# Cpcis_connectors_P1_P2_P3.net
KiCad netlist of a schematic drawn in Altium Designer
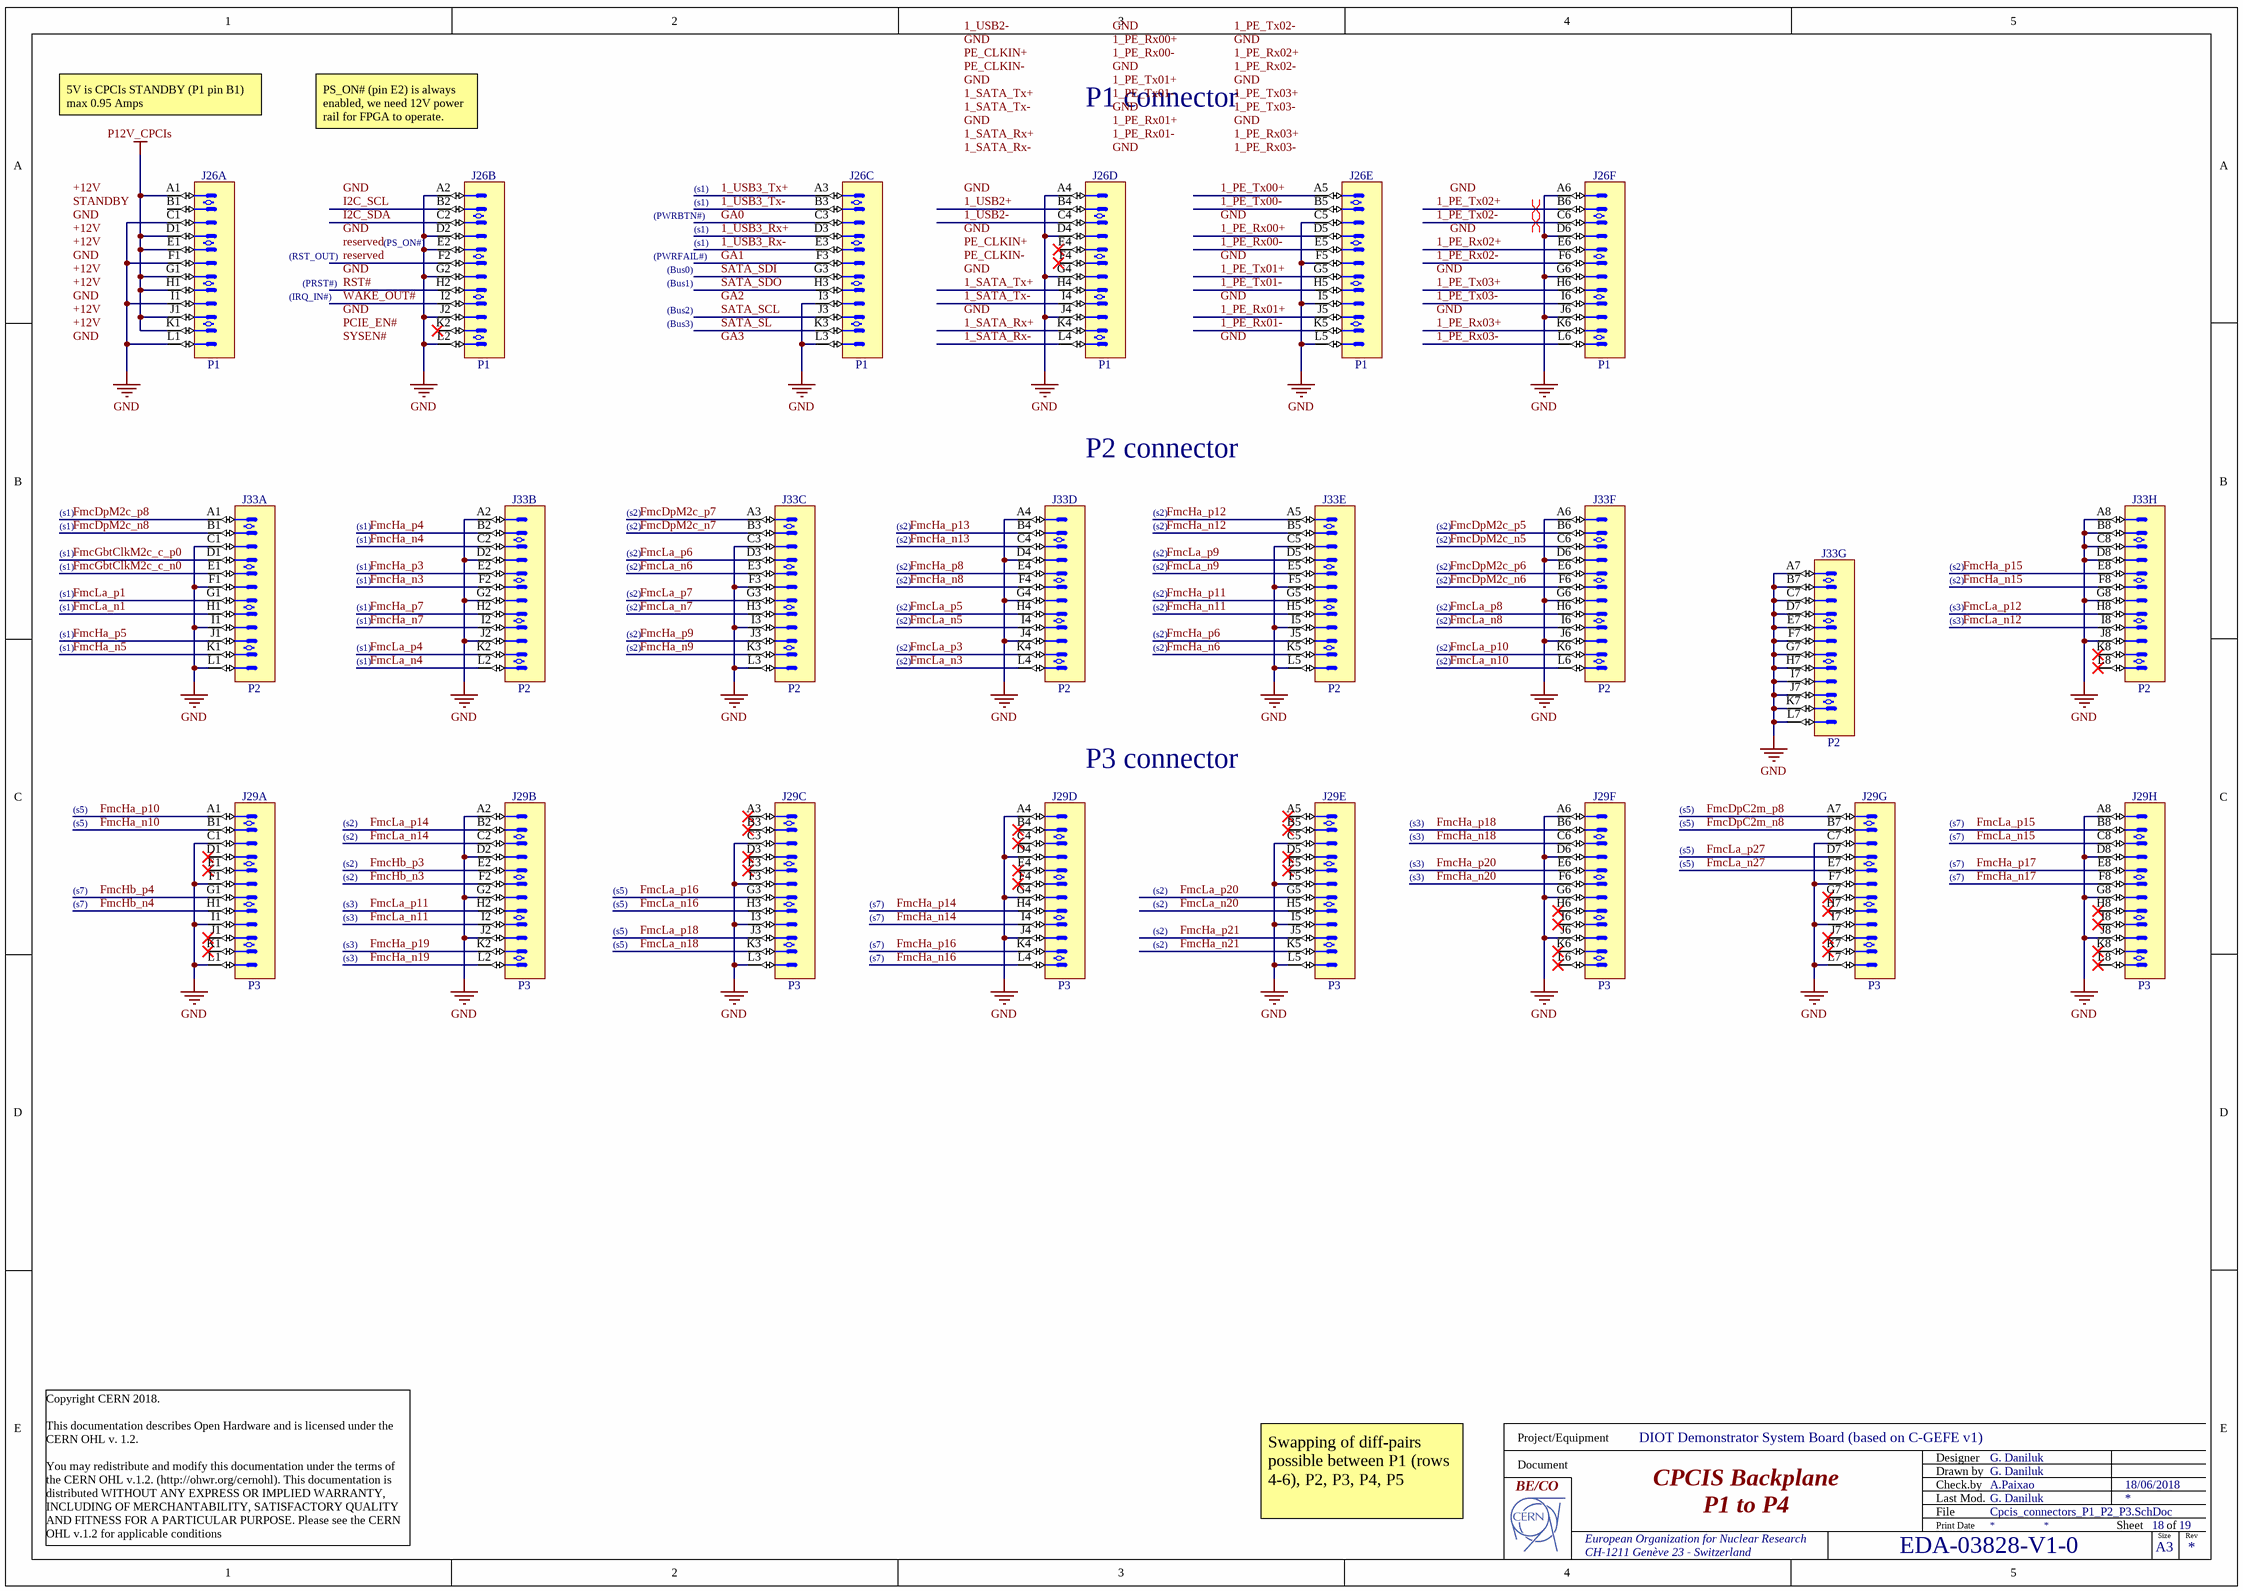
[diagram p0: Cpcis_connectors_P1_P2_P3.SchDoc]

(export (version "E")
  (design (tool "Eeschema 10.0.6"))
  (components
    (comp (ref "J26")
      (value "P1")
      (footprint "AMPHENOL_10052825-101LF")
      (description "72 Contacts Header, 6 Columns, 4 Pairs per Column")
      (fields
        (field (name "PART NUMBER") "AMPHENOL_10052825-101LF")
        (field (name "MANUFACTURER") "AMPHENOL")
        (field (name "AUTHOR") "CERN DEM MR")
      )
      (libsource (lib "Connectors") (part "AMPHENOL_10052825-101LF"))
    )
    (comp (ref "J29")
      (value "P3")
      (footprint "AMPHENOL_10052837-101LF")
      (description "96 Contacts Header, 8 Columns, 4 Pairs per Column")
      (fields
        (field (name "PART NUMBER") "AMPHENOL_10052837-101LF")
        (field (name "MANUFACTURER") "AMPHENOL")
        (field (name "AUTHOR") "CERN DEM MR")
      )
      (libsource (lib "Connectors") (part "AMPHENOL_10052837-101LF"))
    )
    (comp (ref "J33")
      (value "P2")
      (footprint "AMPHENOL_10052837-101LF")
      (description "96 Contacts Header, 8 Columns, 4 Pairs per Column")
      (fields
        (field (name "PART NUMBER") "AMPHENOL_10052837-101LF")
        (field (name "MANUFACTURER") "AMPHENOL")
        (field (name "AUTHOR") "CERN DEM MR")
      )
      (libsource (lib "Connectors") (part "AMPHENOL_10052837-101LF"))
    )
  )
  (nets
    (net (code "2") (name "/1_PE_Rx00+") (class "Default")
      (node (ref "J26") (pin "D5") (pinfunction "D5_D5") (pintype "bidirectional"))
    )
    (net (code "3") (name "/1_PE_Rx00-") (class "Default")
      (node (ref "J26") (pin "E5") (pinfunction "E5_E5") (pintype "bidirectional"))
    )
    (net (code "4") (name "/1_PE_Rx01+") (class "Default")
      (node (ref "J26") (pin "J5") (pinfunction "J5_J5") (pintype "bidirectional"))
    )
    (net (code "5") (name "/1_PE_Rx01-") (class "Default")
      (node (ref "J26") (pin "K5") (pinfunction "K5_K5") (pintype "bidirectional"))
    )
    (net (code "6") (name "/1_PE_Rx02+") (class "Default")
      (node (ref "J26") (pin "E6") (pinfunction "E6_E6") (pintype "bidirectional"))
    )
    (net (code "7") (name "/1_PE_Rx02-") (class "Default")
      (node (ref "J26") (pin "F6") (pinfunction "F6_F6") (pintype "bidirectional"))
    )
    (net (code "8") (name "/1_PE_Rx03+") (class "Default")
      (node (ref "J26") (pin "K6") (pinfunction "K6_K6") (pintype "bidirectional"))
    )
    (net (code "9") (name "/1_PE_Rx03-") (class "Default")
      (node (ref "J26") (pin "L6") (pinfunction "L6_L6") (pintype "bidirectional"))
    )
    (net (code "10") (name "/1_PE_Tx00+") (class "Default")
      (node (ref "J26") (pin "A5") (pinfunction "A5_A5") (pintype "bidirectional"))
    )
    (net (code "11") (name "/1_PE_Tx00-") (class "Default")
      (node (ref "J26") (pin "B5") (pinfunction "B5_B5") (pintype "bidirectional"))
    )
    (net (code "12") (name "/1_PE_Tx01+") (class "Default")
      (node (ref "J26") (pin "G5") (pinfunction "G5_G5") (pintype "bidirectional"))
    )
    (net (code "13") (name "/1_PE_Tx01-") (class "Default")
      (node (ref "J26") (pin "H5") (pinfunction "H5_H5") (pintype "bidirectional"))
    )
    (net (code "14") (name "/1_PE_Tx02+") (class "Default")
      (node (ref "J26") (pin "B6") (pinfunction "B6_B6") (pintype "bidirectional"))
    )
    (net (code "15") (name "/1_PE_Tx02-") (class "Default")
      (node (ref "J26") (pin "C6") (pinfunction "C6_C6") (pintype "bidirectional"))
    )
    (net (code "16") (name "/1_PE_Tx03+") (class "Default")
      (node (ref "J26") (pin "H6") (pinfunction "H6_H6") (pintype "bidirectional"))
    )
    (net (code "17") (name "/1_PE_Tx03-") (class "Default")
      (node (ref "J26") (pin "I6") (pinfunction "I6_I6") (pintype "bidirectional"))
    )
    (net (code "18") (name "/1_SATA_Rx+") (class "Default")
      (node (ref "J26") (pin "K4") (pinfunction "K4_K4") (pintype "bidirectional"))
    )
    (net (code "19") (name "/1_SATA_Rx-") (class "Default")
      (node (ref "J26") (pin "L4") (pinfunction "L4_L4") (pintype "bidirectional"))
    )
    (net (code "20") (name "/1_SATA_Tx+") (class "Default")
      (node (ref "J26") (pin "H4") (pinfunction "H4_H4") (pintype "bidirectional"))
    )
    (net (code "21") (name "/1_SATA_Tx-") (class "Default")
      (node (ref "J26") (pin "I4") (pinfunction "I4_I4") (pintype "bidirectional"))
    )
    (net (code "22") (name "/1_USB2+") (class "Default")
      (node (ref "J26") (pin "B4") (pinfunction "B4_B4") (pintype "bidirectional"))
    )
    (net (code "23") (name "/1_USB2-") (class "Default")
      (node (ref "J26") (pin "C4") (pinfunction "C4_C4") (pintype "bidirectional"))
    )
    (net (code "24") (name "/1_USB3_Rx+") (class "Default")
      (node (ref "J26") (pin "D3") (pinfunction "D3_D3") (pintype "bidirectional"))
    )
    (net (code "25") (name "/1_USB3_Rx-") (class "Default")
      (node (ref "J26") (pin "E3") (pinfunction "E3_E3") (pintype "bidirectional"))
    )
    (net (code "26") (name "/1_USB3_Tx+") (class "Default")
      (node (ref "J26") (pin "A3") (pinfunction "A3_A3") (pintype "bidirectional"))
    )
    (net (code "27") (name "/1_USB3_Tx-") (class "Default")
      (node (ref "J26") (pin "B3") (pinfunction "B3_B3") (pintype "bidirectional"))
    )
    (net (code "28") (name "/FmcDpC2m_n8") (class "Default")
      (node (ref "J29") (pin "B7") (pinfunction "B7_B7") (pintype "bidirectional"))
    )
    (net (code "29") (name "/FmcDpC2m_p8") (class "Default")
      (node (ref "J29") (pin "A7") (pinfunction "A7_A7") (pintype "bidirectional"))
    )
    (net (code "30") (name "/FmcDpM2c_n5") (class "Default")
      (node (ref "J33") (pin "C6") (pinfunction "C6_C6") (pintype "bidirectional"))
    )
    (net (code "31") (name "/FmcDpM2c_n6") (class "Default")
      (node (ref "J33") (pin "F6") (pinfunction "F6_F6") (pintype "bidirectional"))
    )
    (net (code "32") (name "/FmcDpM2c_n7") (class "Default")
      (node (ref "J33") (pin "B3") (pinfunction "B3_B3") (pintype "bidirectional"))
    )
    (net (code "33") (name "/FmcDpM2c_n8") (class "Default")
      (node (ref "J33") (pin "B1") (pinfunction "B1_B1") (pintype "bidirectional"))
    )
    (net (code "34") (name "/FmcDpM2c_p5") (class "Default")
      (node (ref "J33") (pin "B6") (pinfunction "B6_B6") (pintype "bidirectional"))
    )
    (net (code "35") (name "/FmcDpM2c_p6") (class "Default")
      (node (ref "J33") (pin "E6") (pinfunction "E6_E6") (pintype "bidirectional"))
    )
    (net (code "36") (name "/FmcDpM2c_p7") (class "Default")
      (node (ref "J33") (pin "A3") (pinfunction "A3_A3") (pintype "bidirectional"))
    )
    (net (code "37") (name "/FmcDpM2c_p8") (class "Default")
      (node (ref "J33") (pin "A1") (pinfunction "A1_A1") (pintype "bidirectional"))
    )
    (net (code "38") (name "/FmcGbtClkM2c_c_n0") (class "Default")
      (node (ref "J33") (pin "E1") (pinfunction "E1_E1") (pintype "bidirectional"))
    )
    (net (code "39") (name "/FmcGbtClkM2c_c_p0") (class "Default")
      (node (ref "J33") (pin "D1") (pinfunction "D1_D1") (pintype "bidirectional"))
    )
    (net (code "40") (name "/FmcHa_n3") (class "Default")
      (node (ref "J33") (pin "F2") (pinfunction "F2_F2") (pintype "bidirectional"))
    )
    (net (code "41") (name "/FmcHa_n4") (class "Default")
      (node (ref "J33") (pin "C2") (pinfunction "C2_C2") (pintype "bidirectional"))
    )
    (net (code "42") (name "/FmcHa_n5") (class "Default")
      (node (ref "J33") (pin "K1") (pinfunction "K1_K1") (pintype "bidirectional"))
    )
    (net (code "43") (name "/FmcHa_n6") (class "Default")
      (node (ref "J33") (pin "K5") (pinfunction "K5_K5") (pintype "bidirectional"))
    )
    (net (code "44") (name "/FmcHa_n7") (class "Default")
      (node (ref "J33") (pin "I2") (pinfunction "I2_I2") (pintype "bidirectional"))
    )
    (net (code "45") (name "/FmcHa_n8") (class "Default")
      (node (ref "J33") (pin "F4") (pinfunction "F4_F4") (pintype "bidirectional"))
    )
    (net (code "46") (name "/FmcHa_n9") (class "Default")
      (node (ref "J33") (pin "K3") (pinfunction "K3_K3") (pintype "bidirectional"))
    )
    (net (code "47") (name "/FmcHa_n10") (class "Default")
      (node (ref "J29") (pin "B1") (pinfunction "B1_B1") (pintype "bidirectional"))
    )
    (net (code "48") (name "/FmcHa_n11") (class "Default")
      (node (ref "J33") (pin "H5") (pinfunction "H5_H5") (pintype "bidirectional"))
    )
    (net (code "49") (name "/FmcHa_n12") (class "Default")
      (node (ref "J33") (pin "B5") (pinfunction "B5_B5") (pintype "bidirectional"))
    )
    (net (code "50") (name "/FmcHa_n13") (class "Default")
      (node (ref "J33") (pin "C4") (pinfunction "C4_C4") (pintype "bidirectional"))
    )
    (net (code "51") (name "/FmcHa_n14") (class "Default")
      (node (ref "J29") (pin "I4") (pinfunction "I4_I4") (pintype "bidirectional"))
    )
    (net (code "52") (name "/FmcHa_n15") (class "Default")
      (node (ref "J33") (pin "F8") (pinfunction "F8_F8") (pintype "bidirectional"))
    )
    (net (code "53") (name "/FmcHa_n16") (class "Default")
      (node (ref "J29") (pin "L4") (pinfunction "L4_L4") (pintype "bidirectional"))
    )
    (net (code "54") (name "/FmcHa_n17") (class "Default")
      (node (ref "J29") (pin "F8") (pinfunction "F8_F8") (pintype "bidirectional"))
    )
    (net (code "55") (name "/FmcHa_n18") (class "Default")
      (node (ref "J29") (pin "C6") (pinfunction "C6_C6") (pintype "bidirectional"))
    )
    (net (code "56") (name "/FmcHa_n19") (class "Default")
      (node (ref "J29") (pin "L2") (pinfunction "L2_L2") (pintype "bidirectional"))
    )
    (net (code "57") (name "/FmcHa_n20") (class "Default")
      (node (ref "J29") (pin "F6") (pinfunction "F6_F6") (pintype "bidirectional"))
    )
    (net (code "58") (name "/FmcHa_n21") (class "Default")
      (node (ref "J29") (pin "K5") (pinfunction "K5_K5") (pintype "bidirectional"))
    )
    (net (code "59") (name "/FmcHa_p3") (class "Default")
      (node (ref "J33") (pin "E2") (pinfunction "E2_E2") (pintype "bidirectional"))
    )
    (net (code "60") (name "/FmcHa_p4") (class "Default")
      (node (ref "J33") (pin "B2") (pinfunction "B2_B2") (pintype "bidirectional"))
    )
    (net (code "61") (name "/FmcHa_p5") (class "Default")
      (node (ref "J33") (pin "J1") (pinfunction "J1_J1") (pintype "bidirectional"))
    )
    (net (code "62") (name "/FmcHa_p6") (class "Default")
      (node (ref "J33") (pin "J5") (pinfunction "J5_J5") (pintype "bidirectional"))
    )
    (net (code "63") (name "/FmcHa_p7") (class "Default")
      (node (ref "J33") (pin "H2") (pinfunction "H2_H2") (pintype "bidirectional"))
    )
    (net (code "64") (name "/FmcHa_p8") (class "Default")
      (node (ref "J33") (pin "E4") (pinfunction "E4_E4") (pintype "bidirectional"))
    )
    (net (code "65") (name "/FmcHa_p9") (class "Default")
      (node (ref "J33") (pin "J3") (pinfunction "J3_J3") (pintype "bidirectional"))
    )
    (net (code "66") (name "/FmcHa_p10") (class "Default")
      (node (ref "J29") (pin "A1") (pinfunction "A1_A1") (pintype "bidirectional"))
    )
    (net (code "67") (name "/FmcHa_p11") (class "Default")
      (node (ref "J33") (pin "G5") (pinfunction "G5_G5") (pintype "bidirectional"))
    )
    (net (code "68") (name "/FmcHa_p12") (class "Default")
      (node (ref "J33") (pin "A5") (pinfunction "A5_A5") (pintype "bidirectional"))
    )
    (net (code "69") (name "/FmcHa_p13") (class "Default")
      (node (ref "J33") (pin "B4") (pinfunction "B4_B4") (pintype "bidirectional"))
    )
    (net (code "70") (name "/FmcHa_p14") (class "Default")
      (node (ref "J29") (pin "H4") (pinfunction "H4_H4") (pintype "bidirectional"))
    )
    (net (code "71") (name "/FmcHa_p15") (class "Default")
      (node (ref "J33") (pin "E8") (pinfunction "E8_E8") (pintype "bidirectional"))
    )
    (net (code "72") (name "/FmcHa_p16") (class "Default")
      (node (ref "J29") (pin "K4") (pinfunction "K4_K4") (pintype "bidirectional"))
    )
    (net (code "73") (name "/FmcHa_p17") (class "Default")
      (node (ref "J29") (pin "E8") (pinfunction "E8_E8") (pintype "bidirectional"))
    )
    (net (code "74") (name "/FmcHa_p18") (class "Default")
      (node (ref "J29") (pin "B6") (pinfunction "B6_B6") (pintype "bidirectional"))
    )
    (net (code "75") (name "/FmcHa_p19") (class "Default")
      (node (ref "J29") (pin "K2") (pinfunction "K2_K2") (pintype "bidirectional"))
    )
    (net (code "76") (name "/FmcHa_p20") (class "Default")
      (node (ref "J29") (pin "E6") (pinfunction "E6_E6") (pintype "bidirectional"))
    )
    (net (code "77") (name "/FmcHa_p21") (class "Default")
      (node (ref "J29") (pin "J5") (pinfunction "J5_J5") (pintype "bidirectional"))
    )
    (net (code "78") (name "/FmcHb_n3") (class "Default")
      (node (ref "J29") (pin "F2") (pinfunction "F2_F2") (pintype "bidirectional"))
    )
    (net (code "79") (name "/FmcHb_n4") (class "Default")
      (node (ref "J29") (pin "H1") (pinfunction "H1_H1") (pintype "bidirectional"))
    )
    (net (code "80") (name "/FmcHb_p3") (class "Default")
      (node (ref "J29") (pin "E2") (pinfunction "E2_E2") (pintype "bidirectional"))
    )
    (net (code "81") (name "/FmcHb_p4") (class "Default")
      (node (ref "J29") (pin "G1") (pinfunction "G1_G1") (pintype "bidirectional"))
    )
    (net (code "82") (name "/FmcLa_n1") (class "Default")
      (node (ref "J33") (pin "H1") (pinfunction "H1_H1") (pintype "bidirectional"))
    )
    (net (code "83") (name "/FmcLa_n3") (class "Default")
      (node (ref "J33") (pin "L4") (pinfunction "L4_L4") (pintype "bidirectional"))
    )
    (net (code "84") (name "/FmcLa_n4") (class "Default")
      (node (ref "J33") (pin "L2") (pinfunction "L2_L2") (pintype "bidirectional"))
    )
    (net (code "85") (name "/FmcLa_n5") (class "Default")
      (node (ref "J33") (pin "I4") (pinfunction "I4_I4") (pintype "bidirectional"))
    )
    (net (code "86") (name "/FmcLa_n6") (class "Default")
      (node (ref "J33") (pin "E3") (pinfunction "E3_E3") (pintype "bidirectional"))
    )
    (net (code "87") (name "/FmcLa_n7") (class "Default")
      (node (ref "J33") (pin "H3") (pinfunction "H3_H3") (pintype "bidirectional"))
    )
    (net (code "88") (name "/FmcLa_n8") (class "Default")
      (node (ref "J33") (pin "I6") (pinfunction "I6_I6") (pintype "bidirectional"))
    )
    (net (code "89") (name "/FmcLa_n9") (class "Default")
      (node (ref "J33") (pin "E5") (pinfunction "E5_E5") (pintype "bidirectional"))
    )
    (net (code "90") (name "/FmcLa_n10") (class "Default")
      (node (ref "J33") (pin "L6") (pinfunction "L6_L6") (pintype "bidirectional"))
    )
    (net (code "91") (name "/FmcLa_n11") (class "Default")
      (node (ref "J29") (pin "I2") (pinfunction "I2_I2") (pintype "bidirectional"))
    )
    (net (code "92") (name "/FmcLa_n12") (class "Default")
      (node (ref "J33") (pin "I8") (pinfunction "I8_I8") (pintype "bidirectional"))
    )
    (net (code "93") (name "/FmcLa_n14") (class "Default")
      (node (ref "J29") (pin "C2") (pinfunction "C2_C2") (pintype "bidirectional"))
    )
    (net (code "94") (name "/FmcLa_n15") (class "Default")
      (node (ref "J29") (pin "C8") (pinfunction "C8_C8") (pintype "bidirectional"))
    )
    (net (code "95") (name "/FmcLa_n16") (class "Default")
      (node (ref "J29") (pin "H3") (pinfunction "H3_H3") (pintype "bidirectional"))
    )
    (net (code "96") (name "/FmcLa_n18") (class "Default")
      (node (ref "J29") (pin "K3") (pinfunction "K3_K3") (pintype "bidirectional"))
    )
    (net (code "97") (name "/FmcLa_n20") (class "Default")
      (node (ref "J29") (pin "H5") (pinfunction "H5_H5") (pintype "bidirectional"))
    )
    (net (code "98") (name "/FmcLa_n27") (class "Default")
      (node (ref "J29") (pin "E7") (pinfunction "E7_E7") (pintype "bidirectional"))
    )
    (net (code "99") (name "/FmcLa_p1") (class "Default")
      (node (ref "J33") (pin "G1") (pinfunction "G1_G1") (pintype "bidirectional"))
    )
    (net (code "100") (name "/FmcLa_p3") (class "Default")
      (node (ref "J33") (pin "K4") (pinfunction "K4_K4") (pintype "bidirectional"))
    )
    (net (code "101") (name "/FmcLa_p4") (class "Default")
      (node (ref "J33") (pin "K2") (pinfunction "K2_K2") (pintype "bidirectional"))
    )
    (net (code "102") (name "/FmcLa_p5") (class "Default")
      (node (ref "J33") (pin "H4") (pinfunction "H4_H4") (pintype "bidirectional"))
    )
    (net (code "103") (name "/FmcLa_p6") (class "Default")
      (node (ref "J33") (pin "D3") (pinfunction "D3_D3") (pintype "bidirectional"))
    )
    (net (code "104") (name "/FmcLa_p7") (class "Default")
      (node (ref "J33") (pin "G3") (pinfunction "G3_G3") (pintype "bidirectional"))
    )
    (net (code "105") (name "/FmcLa_p8") (class "Default")
      (node (ref "J33") (pin "H6") (pinfunction "H6_H6") (pintype "bidirectional"))
    )
    (net (code "106") (name "/FmcLa_p9") (class "Default")
      (node (ref "J33") (pin "D5") (pinfunction "D5_D5") (pintype "bidirectional"))
    )
    (net (code "107") (name "/FmcLa_p10") (class "Default")
      (node (ref "J33") (pin "K6") (pinfunction "K6_K6") (pintype "bidirectional"))
    )
    (net (code "108") (name "/FmcLa_p11") (class "Default")
      (node (ref "J29") (pin "H2") (pinfunction "H2_H2") (pintype "bidirectional"))
    )
    (net (code "109") (name "/FmcLa_p12") (class "Default")
      (node (ref "J33") (pin "H8") (pinfunction "H8_H8") (pintype "bidirectional"))
    )
    (net (code "110") (name "/FmcLa_p14") (class "Default")
      (node (ref "J29") (pin "B2") (pinfunction "B2_B2") (pintype "bidirectional"))
    )
    (net (code "111") (name "/FmcLa_p15") (class "Default")
      (node (ref "J29") (pin "B8") (pinfunction "B8_B8") (pintype "bidirectional"))
    )
    (net (code "112") (name "/FmcLa_p16") (class "Default")
      (node (ref "J29") (pin "G3") (pinfunction "G3_G3") (pintype "bidirectional"))
    )
    (net (code "113") (name "/FmcLa_p18") (class "Default")
      (node (ref "J29") (pin "J3") (pinfunction "J3_J3") (pintype "bidirectional"))
    )
    (net (code "114") (name "/FmcLa_p20") (class "Default")
      (node (ref "J29") (pin "G5") (pinfunction "G5_G5") (pintype "bidirectional"))
    )
    (net (code "115") (name "/FmcLa_p27") (class "Default")
      (node (ref "J29") (pin "D7") (pinfunction "D7_D7") (pintype "bidirectional"))
    )
    (net (code "116") (name "/GA0") (class "Default")
      (node (ref "J26") (pin "C3") (pinfunction "C3_C3") (pintype "bidirectional"))
    )
    (net (code "117") (name "/GA1") (class "Default")
      (node (ref "J26") (pin "F3") (pinfunction "F3_F3") (pintype "bidirectional"))
    )
    (net (code "120") (name "/I2C_SCL") (class "Default")
      (node (ref "J26") (pin "B2") (pinfunction "B2_B2") (pintype "bidirectional"))
    )
    (net (code "121") (name "/I2C_SDA") (class "Default")
      (node (ref "J26") (pin "C2") (pinfunction "C2_C2") (pintype "bidirectional"))
    )
    (net (code "125") (name "/RST#") (class "Default")
      (node (ref "J26") (pin "H2") (pinfunction "H2_H2") (pintype "bidirectional"))
    )
    (net (code "126") (name "/SATA_SCL") (class "Default")
      (node (ref "J26") (pin "J3") (pinfunction "J3_J3") (pintype "bidirectional"))
    )
    (net (code "127") (name "/SATA_SDI") (class "Default")
      (node (ref "J26") (pin "G3") (pinfunction "G3_G3") (pintype "bidirectional"))
    )
    (net (code "128") (name "/SATA_SDO") (class "Default")
      (node (ref "J26") (pin "H3") (pinfunction "H3_H3") (pintype "bidirectional"))
    )
    (net (code "129") (name "/SATA_SL") (class "Default")
      (node (ref "J26") (pin "K3") (pinfunction "K3_K3") (pintype "bidirectional"))
    )
    (net (code "132") (name "/WAKE_OUT#") (class "Default")
      (node (ref "J26") (pin "I2") (pinfunction "I2_I2") (pintype "bidirectional"))
    )
    (net (code "133") (name "/reserved") (class "Default")
      (node (ref "J26") (pin "F2") (pinfunction "F2_F2") (pintype "bidirectional"))
    )
    (net (code "134") (name "GND") (class "Default")
      (node (ref "J26") (pin "A2") (pinfunction "A2_A2") (pintype "bidirectional"))
      (node (ref "J26") (pin "A4") (pinfunction "A4_A4") (pintype "bidirectional"))
      (node (ref "J26") (pin "A6") (pinfunction "A6_A6") (pintype "bidirectional"))
      (node (ref "J26") (pin "C1") (pinfunction "C1_C1") (pintype "bidirectional"))
      (node (ref "J26") (pin "C5") (pinfunction "C5_C5") (pintype "bidirectional"))
      (node (ref "J26") (pin "D2") (pinfunction "D2_D2") (pintype "bidirectional"))
      (node (ref "J26") (pin "D4") (pinfunction "D4_D4") (pintype "bidirectional"))
      (node (ref "J26") (pin "D6") (pinfunction "D6_D6") (pintype "bidirectional"))
      (node (ref "J26") (pin "E2") (pinfunction "E2_E2") (pintype "bidirectional"))
      (node (ref "J26") (pin "F1") (pinfunction "F1_F1") (pintype "bidirectional"))
      (node (ref "J26") (pin "F5") (pinfunction "F5_F5") (pintype "bidirectional"))
      (node (ref "J26") (pin "G2") (pinfunction "G2_G2") (pintype "bidirectional"))
      (node (ref "J26") (pin "G4") (pinfunction "G4_G4") (pintype "bidirectional"))
      (node (ref "J26") (pin "G6") (pinfunction "G6_G6") (pintype "bidirectional"))
      (node (ref "J26") (pin "I1") (pinfunction "I1_I1") (pintype "bidirectional"))
      (node (ref "J26") (pin "I3") (pinfunction "I3_I3") (pintype "bidirectional"))
      (node (ref "J26") (pin "I5") (pinfunction "I5_I5") (pintype "bidirectional"))
      (node (ref "J26") (pin "J2") (pinfunction "J2_J2") (pintype "bidirectional"))
      (node (ref "J26") (pin "J4") (pinfunction "J4_J4") (pintype "bidirectional"))
      (node (ref "J26") (pin "J6") (pinfunction "J6_J6") (pintype "bidirectional"))
      (node (ref "J26") (pin "L1") (pinfunction "L1_L1") (pintype "bidirectional"))
      (node (ref "J26") (pin "L2") (pinfunction "L2_L2") (pintype "bidirectional"))
      (node (ref "J26") (pin "L3") (pinfunction "L3_L3") (pintype "bidirectional"))
      (node (ref "J26") (pin "L5") (pinfunction "L5_L5") (pintype "bidirectional"))
      (node (ref "J29") (pin "A2") (pinfunction "A2_A2") (pintype "bidirectional"))
      (node (ref "J29") (pin "A4") (pinfunction "A4_A4") (pintype "bidirectional"))
      (node (ref "J29") (pin "A6") (pinfunction "A6_A6") (pintype "bidirectional"))
      (node (ref "J29") (pin "A8") (pinfunction "A8_A8") (pintype "bidirectional"))
      (node (ref "J29") (pin "C1") (pinfunction "C1_C1") (pintype "bidirectional"))
      (node (ref "J29") (pin "C3") (pinfunction "C3_C3") (pintype "bidirectional"))
      (node (ref "J29") (pin "C5") (pinfunction "C5_C5") (pintype "bidirectional"))
      (node (ref "J29") (pin "C7") (pinfunction "C7_C7") (pintype "bidirectional"))
      (node (ref "J29") (pin "D2") (pinfunction "D2_D2") (pintype "bidirectional"))
      (node (ref "J29") (pin "D4") (pinfunction "D4_D4") (pintype "bidirectional"))
      (node (ref "J29") (pin "D6") (pinfunction "D6_D6") (pintype "bidirectional"))
      (node (ref "J29") (pin "D8") (pinfunction "D8_D8") (pintype "bidirectional"))
      (node (ref "J29") (pin "F1") (pinfunction "F1_F1") (pintype "bidirectional"))
      (node (ref "J29") (pin "F3") (pinfunction "F3_F3") (pintype "bidirectional"))
      (node (ref "J29") (pin "F5") (pinfunction "F5_F5") (pintype "bidirectional"))
      (node (ref "J29") (pin "F7") (pinfunction "F7_F7") (pintype "bidirectional"))
      (node (ref "J29") (pin "G2") (pinfunction "G2_G2") (pintype "bidirectional"))
      (node (ref "J29") (pin "G4") (pinfunction "G4_G4") (pintype "bidirectional"))
      (node (ref "J29") (pin "G6") (pinfunction "G6_G6") (pintype "bidirectional"))
      (node (ref "J29") (pin "G8") (pinfunction "G8_G8") (pintype "bidirectional"))
      (node (ref "J29") (pin "I1") (pinfunction "I1_I1") (pintype "bidirectional"))
      (node (ref "J29") (pin "I3") (pinfunction "I3_I3") (pintype "bidirectional"))
      (node (ref "J29") (pin "I5") (pinfunction "I5_I5") (pintype "bidirectional"))
      (node (ref "J29") (pin "I7") (pinfunction "I7_I7") (pintype "bidirectional"))
      (node (ref "J29") (pin "J2") (pinfunction "J2_J2") (pintype "bidirectional"))
      (node (ref "J29") (pin "J4") (pinfunction "J4_J4") (pintype "bidirectional"))
      (node (ref "J29") (pin "J6") (pinfunction "J6_J6") (pintype "bidirectional"))
      (node (ref "J29") (pin "J8") (pinfunction "J8_J8") (pintype "bidirectional"))
      (node (ref "J29") (pin "L1") (pinfunction "L1_L1") (pintype "bidirectional"))
      (node (ref "J29") (pin "L3") (pinfunction "L3_L3") (pintype "bidirectional"))
      (node (ref "J29") (pin "L5") (pinfunction "L5_L5") (pintype "bidirectional"))
      (node (ref "J29") (pin "L7") (pinfunction "L7_L7") (pintype "bidirectional"))
      (node (ref "J33") (pin "A2") (pinfunction "A2_A2") (pintype "bidirectional"))
      (node (ref "J33") (pin "A4") (pinfunction "A4_A4") (pintype "bidirectional"))
      (node (ref "J33") (pin "A6") (pinfunction "A6_A6") (pintype "bidirectional"))
      (node (ref "J33") (pin "A7") (pinfunction "A7_A7") (pintype "bidirectional"))
      (node (ref "J33") (pin "A8") (pinfunction "A8_A8") (pintype "bidirectional"))
      (node (ref "J33") (pin "B7") (pinfunction "B7_B7") (pintype "bidirectional"))
      (node (ref "J33") (pin "B8") (pinfunction "B8_B8") (pintype "bidirectional"))
      (node (ref "J33") (pin "C1") (pinfunction "C1_C1") (pintype "bidirectional"))
      (node (ref "J33") (pin "C3") (pinfunction "C3_C3") (pintype "bidirectional"))
      (node (ref "J33") (pin "C5") (pinfunction "C5_C5") (pintype "bidirectional"))
      (node (ref "J33") (pin "C7") (pinfunction "C7_C7") (pintype "bidirectional"))
      (node (ref "J33") (pin "C8") (pinfunction "C8_C8") (pintype "bidirectional"))
      (node (ref "J33") (pin "D2") (pinfunction "D2_D2") (pintype "bidirectional"))
      (node (ref "J33") (pin "D4") (pinfunction "D4_D4") (pintype "bidirectional"))
      (node (ref "J33") (pin "D6") (pinfunction "D6_D6") (pintype "bidirectional"))
      (node (ref "J33") (pin "D7") (pinfunction "D7_D7") (pintype "bidirectional"))
      (node (ref "J33") (pin "D8") (pinfunction "D8_D8") (pintype "bidirectional"))
      (node (ref "J33") (pin "E7") (pinfunction "E7_E7") (pintype "bidirectional"))
      (node (ref "J33") (pin "F1") (pinfunction "F1_F1") (pintype "bidirectional"))
      (node (ref "J33") (pin "F3") (pinfunction "F3_F3") (pintype "bidirectional"))
      (node (ref "J33") (pin "F5") (pinfunction "F5_F5") (pintype "bidirectional"))
      (node (ref "J33") (pin "F7") (pinfunction "F7_F7") (pintype "bidirectional"))
      (node (ref "J33") (pin "G2") (pinfunction "G2_G2") (pintype "bidirectional"))
      (node (ref "J33") (pin "G4") (pinfunction "G4_G4") (pintype "bidirectional"))
      (node (ref "J33") (pin "G6") (pinfunction "G6_G6") (pintype "bidirectional"))
      (node (ref "J33") (pin "G7") (pinfunction "G7_G7") (pintype "bidirectional"))
      (node (ref "J33") (pin "G8") (pinfunction "G8_G8") (pintype "bidirectional"))
      (node (ref "J33") (pin "H7") (pinfunction "H7_H7") (pintype "bidirectional"))
      (node (ref "J33") (pin "I1") (pinfunction "I1_I1") (pintype "bidirectional"))
      (node (ref "J33") (pin "I3") (pinfunction "I3_I3") (pintype "bidirectional"))
      (node (ref "J33") (pin "I5") (pinfunction "I5_I5") (pintype "bidirectional"))
      (node (ref "J33") (pin "I7") (pinfunction "I7_I7") (pintype "bidirectional"))
      (node (ref "J33") (pin "J2") (pinfunction "J2_J2") (pintype "bidirectional"))
      (node (ref "J33") (pin "J4") (pinfunction "J4_J4") (pintype "bidirectional"))
      (node (ref "J33") (pin "J6") (pinfunction "J6_J6") (pintype "bidirectional"))
      (node (ref "J33") (pin "J7") (pinfunction "J7_J7") (pintype "bidirectional"))
      (node (ref "J33") (pin "J8") (pinfunction "J8_J8") (pintype "bidirectional"))
      (node (ref "J33") (pin "K7") (pinfunction "K7_K7") (pintype "bidirectional"))
      (node (ref "J33") (pin "L1") (pinfunction "L1_L1") (pintype "bidirectional"))
      (node (ref "J33") (pin "L3") (pinfunction "L3_L3") (pintype "bidirectional"))
      (node (ref "J33") (pin "L5") (pinfunction "L5_L5") (pintype "bidirectional"))
      (node (ref "J33") (pin "L7") (pinfunction "L7_L7") (pintype "bidirectional"))
    )
    (net (code "135") (name "P12V_CPCIs") (class "Default")
      (node (ref "J26") (pin "A1") (pinfunction "A1_A1") (pintype "bidirectional"))
      (node (ref "J26") (pin "D1") (pinfunction "D1_D1") (pintype "bidirectional"))
      (node (ref "J26") (pin "E1") (pinfunction "E1_E1") (pintype "bidirectional"))
      (node (ref "J26") (pin "G1") (pinfunction "G1_G1") (pintype "bidirectional"))
      (node (ref "J26") (pin "H1") (pinfunction "H1_H1") (pintype "bidirectional"))
      (node (ref "J26") (pin "J1") (pinfunction "J1_J1") (pintype "bidirectional"))
      (node (ref "J26") (pin "K1") (pinfunction "K1_K1") (pintype "bidirectional"))
    )
    (net (code "136") (name "unconnected-(J26-PadB1)") (class "Default")
      (node (ref "J26") (pin "B1") (pinfunction "B1_B1") (pintype "bidirectional"))
    )
    (net (code "137") (name "unconnected-(J26-PadE4)") (class "Default")
      (node (ref "J26") (pin "E4") (pinfunction "E4_E4") (pintype "bidirectional+no_connect"))
    )
    (net (code "138") (name "unconnected-(J26-PadF4)") (class "Default")
      (node (ref "J26") (pin "F4") (pinfunction "F4_F4") (pintype "bidirectional+no_connect"))
    )
    (net (code "139") (name "unconnected-(J26-PadK2)") (class "Default")
      (node (ref "J26") (pin "K2") (pinfunction "K2_K2") (pintype "bidirectional+no_connect"))
    )
    (net (code "140") (name "unconnected-(J29-PadA3)") (class "Default")
      (node (ref "J29") (pin "A3") (pinfunction "A3_A3") (pintype "bidirectional+no_connect"))
    )
    (net (code "141") (name "unconnected-(J29-PadA5)") (class "Default")
      (node (ref "J29") (pin "A5") (pinfunction "A5_A5") (pintype "bidirectional+no_connect"))
    )
    (net (code "142") (name "unconnected-(J29-PadB3)") (class "Default")
      (node (ref "J29") (pin "B3") (pinfunction "B3_B3") (pintype "bidirectional+no_connect"))
    )
    (net (code "143") (name "unconnected-(J29-PadB4)") (class "Default")
      (node (ref "J29") (pin "B4") (pinfunction "B4_B4") (pintype "bidirectional+no_connect"))
    )
    (net (code "144") (name "unconnected-(J29-PadB5)") (class "Default")
      (node (ref "J29") (pin "B5") (pinfunction "B5_B5") (pintype "bidirectional+no_connect"))
    )
    (net (code "145") (name "unconnected-(J29-PadC4)") (class "Default")
      (node (ref "J29") (pin "C4") (pinfunction "C4_C4") (pintype "bidirectional+no_connect"))
    )
    (net (code "146") (name "unconnected-(J29-PadD1)") (class "Default")
      (node (ref "J29") (pin "D1") (pinfunction "D1_D1") (pintype "bidirectional+no_connect"))
    )
    (net (code "147") (name "unconnected-(J29-PadD3)") (class "Default")
      (node (ref "J29") (pin "D3") (pinfunction "D3_D3") (pintype "bidirectional+no_connect"))
    )
    (net (code "148") (name "unconnected-(J29-PadD5)") (class "Default")
      (node (ref "J29") (pin "D5") (pinfunction "D5_D5") (pintype "bidirectional+no_connect"))
    )
    (net (code "149") (name "unconnected-(J29-PadE1)") (class "Default")
      (node (ref "J29") (pin "E1") (pinfunction "E1_E1") (pintype "bidirectional+no_connect"))
    )
    (net (code "150") (name "unconnected-(J29-PadE3)") (class "Default")
      (node (ref "J29") (pin "E3") (pinfunction "E3_E3") (pintype "bidirectional+no_connect"))
    )
    (net (code "151") (name "unconnected-(J29-PadE4)") (class "Default")
      (node (ref "J29") (pin "E4") (pinfunction "E4_E4") (pintype "bidirectional+no_connect"))
    )
    (net (code "152") (name "unconnected-(J29-PadE5)") (class "Default")
      (node (ref "J29") (pin "E5") (pinfunction "E5_E5") (pintype "bidirectional+no_connect"))
    )
    (net (code "153") (name "unconnected-(J29-PadF4)") (class "Default")
      (node (ref "J29") (pin "F4") (pinfunction "F4_F4") (pintype "bidirectional+no_connect"))
    )
    (net (code "154") (name "unconnected-(J29-PadG7)") (class "Default")
      (node (ref "J29") (pin "G7") (pinfunction "G7_G7") (pintype "bidirectional+no_connect"))
    )
    (net (code "155") (name "unconnected-(J29-PadH6)") (class "Default")
      (node (ref "J29") (pin "H6") (pinfunction "H6_H6") (pintype "bidirectional+no_connect"))
    )
    (net (code "156") (name "unconnected-(J29-PadH7)") (class "Default")
      (node (ref "J29") (pin "H7") (pinfunction "H7_H7") (pintype "bidirectional+no_connect"))
    )
    (net (code "157") (name "unconnected-(J29-PadH8)") (class "Default")
      (node (ref "J29") (pin "H8") (pinfunction "H8_H8") (pintype "bidirectional+no_connect"))
    )
    (net (code "158") (name "unconnected-(J29-PadI6)") (class "Default")
      (node (ref "J29") (pin "I6") (pinfunction "I6_I6") (pintype "bidirectional+no_connect"))
    )
    (net (code "159") (name "unconnected-(J29-PadI8)") (class "Default")
      (node (ref "J29") (pin "I8") (pinfunction "I8_I8") (pintype "bidirectional+no_connect"))
    )
    (net (code "160") (name "unconnected-(J29-PadJ1)") (class "Default")
      (node (ref "J29") (pin "J1") (pinfunction "J1_J1") (pintype "bidirectional+no_connect"))
    )
    (net (code "161") (name "unconnected-(J29-PadJ7)") (class "Default")
      (node (ref "J29") (pin "J7") (pinfunction "J7_J7") (pintype "bidirectional+no_connect"))
    )
    (net (code "162") (name "unconnected-(J29-PadK1)") (class "Default")
      (node (ref "J29") (pin "K1") (pinfunction "K1_K1") (pintype "bidirectional+no_connect"))
    )
    (net (code "163") (name "unconnected-(J29-PadK6)") (class "Default")
      (node (ref "J29") (pin "K6") (pinfunction "K6_K6") (pintype "bidirectional+no_connect"))
    )
    (net (code "164") (name "unconnected-(J29-PadK7)") (class "Default")
      (node (ref "J29") (pin "K7") (pinfunction "K7_K7") (pintype "bidirectional+no_connect"))
    )
    (net (code "165") (name "unconnected-(J29-PadK8)") (class "Default")
      (node (ref "J29") (pin "K8") (pinfunction "K8_K8") (pintype "bidirectional+no_connect"))
    )
    (net (code "166") (name "unconnected-(J29-PadL6)") (class "Default")
      (node (ref "J29") (pin "L6") (pinfunction "L6_L6") (pintype "bidirectional+no_connect"))
    )
    (net (code "167") (name "unconnected-(J29-PadL8)") (class "Default")
      (node (ref "J29") (pin "L8") (pinfunction "L8_L8") (pintype "bidirectional+no_connect"))
    )
    (net (code "168") (name "unconnected-(J33-PadK8)") (class "Default")
      (node (ref "J33") (pin "K8") (pinfunction "K8_K8") (pintype "bidirectional+no_connect"))
    )
    (net (code "169") (name "unconnected-(J33-PadL8)") (class "Default")
      (node (ref "J33") (pin "L8") (pinfunction "L8_L8") (pintype "bidirectional+no_connect"))
    )
  )
)
